# System.net
KiCad netlist of a schematic drawn in Altium Designer
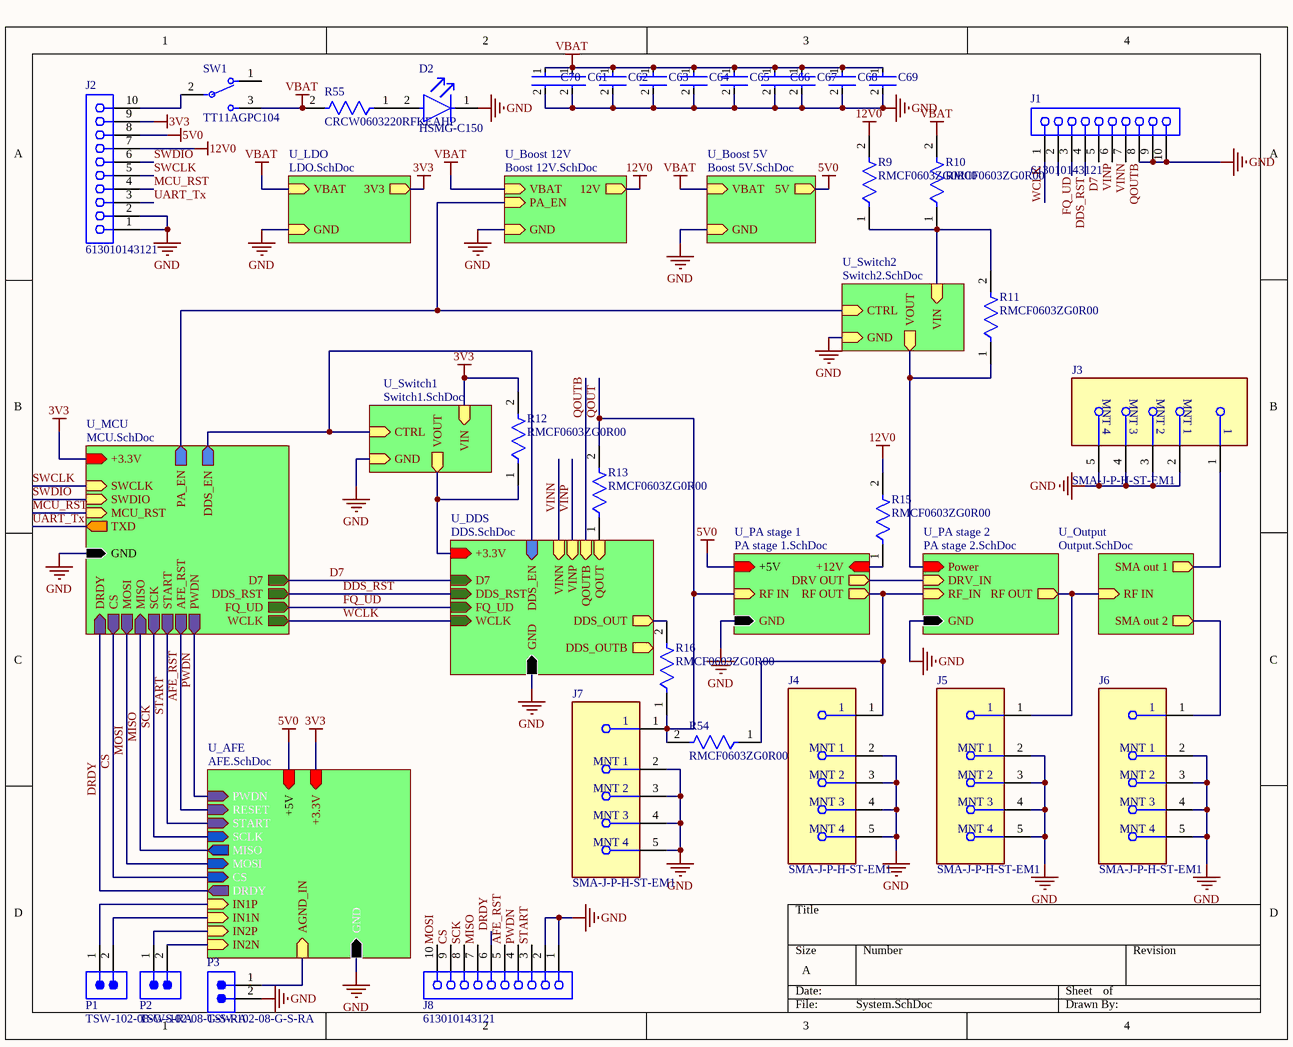
[diagram p0: System.SchDoc]

(export (version "E")
  (design (tool "Eeschema 10.0.6"))
  (components
    (comp (ref "C61")
      (value "GRM21BR60J107ME15K")
      (footprint "FP-GRM21B-0_2-e0_2_0_7-IPC_B")
      (description "Chip Multilayer Ceramic Capacitors for General Purpose, 0805, 100uF, X5R, 15%, 20%, 6.3V")
      (fields (field (name "TOLERANCE") "20%"))
      (libsource (lib "Altium Content Vault") (part "b4654b650e69147ec39a6b967a45e02"))
    )
    (comp (ref "C62")
      (value "GRM21BR60J107ME15K")
      (footprint "FP-GRM21B-0_2-e0_2_0_7-IPC_B")
      (description "Chip Multilayer Ceramic Capacitors for General Purpose, 0805, 100uF, X5R, 15%, 20%, 6.3V")
      (fields (field (name "TOLERANCE") "20%"))
      (libsource (lib "Altium Content Vault") (part "b4654b650e69147ec39a6b967a45e02"))
    )
    (comp (ref "C63")
      (value "GRM21BR60J107ME15K")
      (footprint "FP-GRM21B-0_2-e0_2_0_7-IPC_B")
      (description "Chip Multilayer Ceramic Capacitors for General Purpose, 0805, 100uF, X5R, 15%, 20%, 6.3V")
      (fields (field (name "TOLERANCE") "20%"))
      (libsource (lib "Altium Content Vault") (part "b4654b650e69147ec39a6b967a45e02"))
    )
    (comp (ref "C64")
      (value "GRM21BR60J107ME15K")
      (footprint "FP-GRM21B-0_2-e0_2_0_7-IPC_B")
      (description "Chip Multilayer Ceramic Capacitors for General Purpose, 0805, 100uF, X5R, 15%, 20%, 6.3V")
      (fields (field (name "TOLERANCE") "20%"))
      (libsource (lib "Altium Content Vault") (part "b4654b650e69147ec39a6b967a45e02"))
    )
    (comp (ref "C65")
      (value "GRM21BR60J107ME15K")
      (footprint "FP-GRM21B-0_2-e0_2_0_7-IPC_B")
      (description "Chip Multilayer Ceramic Capacitors for General Purpose, 0805, 100uF, X5R, 15%, 20%, 6.3V")
      (fields (field (name "TOLERANCE") "20%"))
      (libsource (lib "Altium Content Vault") (part "b4654b650e69147ec39a6b967a45e02"))
    )
    (comp (ref "C66")
      (value "GRM21BR60J107ME15K")
      (footprint "FP-GRM21B-0_2-e0_2_0_7-IPC_B")
      (description "Chip Multilayer Ceramic Capacitors for General Purpose, 0805, 100uF, X5R, 15%, 20%, 6.3V")
      (fields (field (name "TOLERANCE") "20%"))
      (libsource (lib "Altium Content Vault") (part "b4654b650e69147ec39a6b967a45e02"))
    )
    (comp (ref "C67")
      (value "GRM21BR60J107ME15K")
      (footprint "FP-GRM21B-0_2-e0_2_0_7-IPC_B")
      (description "Chip Multilayer Ceramic Capacitors for General Purpose, 0805, 100uF, X5R, 15%, 20%, 6.3V")
      (fields (field (name "TOLERANCE") "20%"))
      (libsource (lib "Altium Content Vault") (part "b4654b650e69147ec39a6b967a45e02"))
    )
    (comp (ref "C68")
      (value "GRM21BR60J107ME15K")
      (footprint "FP-GRM21B-0_2-e0_2_0_7-IPC_B")
      (description "Chip Multilayer Ceramic Capacitors for General Purpose, 0805, 100uF, X5R, 15%, 20%, 6.3V")
      (fields (field (name "TOLERANCE") "20%"))
      (libsource (lib "Altium Content Vault") (part "b4654b650e69147ec39a6b967a45e02"))
    )
    (comp (ref "C69")
      (value "GRM21BR60J107ME15K")
      (footprint "FP-GRM21B-0_2-e0_2_0_7-IPC_B")
      (description "Chip Multilayer Ceramic Capacitors for General Purpose, 0805, 100uF, X5R, 15%, 20%, 6.3V")
      (fields (field (name "TOLERANCE") "20%"))
      (libsource (lib "Altium Content Vault") (part "b4654b650e69147ec39a6b967a45e02"))
    )
    (comp (ref "C70")
      (value "GRM21BR60J107ME15K")
      (footprint "FP-GRM21B-0_2-e0_2_0_7-IPC_B")
      (description "Chip Multilayer Ceramic Capacitors for General Purpose, 0805, 100uF, X5R, 15%, 20%, 6.3V")
      (fields (field (name "TOLERANCE") "20%"))
      (libsource (lib "Altium Content Vault") (part "b4654b650e69147ec39a6b967a45e02"))
    )
    (comp (ref "D2")
      (value "HSMG-C150")
      (footprint "FP-HSMG-C150-MFG")
      (description "LED GREEN DIFFUSED 1206 SMD")
      (fields
        (field (name "MANUFACTURER") "Broadcom")
        (field (name "OCTOPART") "https://octopart.com/hsmg-c150-broadcom-71131304")
      )
      (libsource (lib "Altium Content Vault") (part "8706943c75ba83719d021d2fdc84c58"))
    )
    (comp (ref "J1")
      (value "613010143121")
      (footprint "613010143121")
      (libsource (lib "Altium Content Vault") (part "Header_Female_1R_10P"))
    )
    (comp (ref "J2")
      (value "613010143121")
      (footprint "613010143121")
      (libsource (lib "Altium Content Vault") (part "Header_Female_1R_10P"))
    )
    (comp (ref "J3")
      (value "SMA-J-P-H-ST-EM1")
      (footprint "FP-SMA-J-P-H-ST-EM1-MFG")
      (description "CONN SMA JACK STR 50OHM EDGE MNT")
      (libsource (lib "") (part "c65b8a639cdaef1819ea20b5466f8fa_1"))
    )
    (comp (ref "J4")
      (value "SMA-J-P-H-ST-EM1")
      (footprint "FP-SMA-J-P-H-ST-EM1-MFG")
      (description "CONN SMA JACK STR 50OHM EDGE MNT")
      (libsource (lib "Altium Content Vault") (part "c65b8a639cdaef1819ea20b5466f8fa"))
    )
    (comp (ref "J5")
      (value "SMA-J-P-H-ST-EM1")
      (footprint "FP-SMA-J-P-H-ST-EM1-MFG")
      (description "CONN SMA JACK STR 50OHM EDGE MNT")
      (libsource (lib "Altium Content Vault") (part "c65b8a639cdaef1819ea20b5466f8fa"))
    )
    (comp (ref "J6")
      (value "SMA-J-P-H-ST-EM1")
      (footprint "FP-SMA-J-P-H-ST-EM1-MFG")
      (description "CONN SMA JACK STR 50OHM EDGE MNT")
      (libsource (lib "Altium Content Vault") (part "c65b8a639cdaef1819ea20b5466f8fa"))
    )
    (comp (ref "J7")
      (value "SMA-J-P-H-ST-EM1")
      (footprint "FP-SMA-J-P-H-ST-EM1-MFG")
      (description "CONN SMA JACK STR 50OHM EDGE MNT")
      (libsource (lib "Altium Content Vault") (part "c65b8a639cdaef1819ea20b5466f8fa"))
    )
    (comp (ref "J8")
      (value "613010143121")
      (footprint "613010143121")
      (libsource (lib "Altium Content Vault") (part "Header_Female_1R_10P"))
    )
    (comp (ref "P1")
      (value "TSW-102-08-G-S-RA")
      (footprint "SMTC-TSW-102-08-X-S-RA")
      (fields (field (name "MANUFACTURER") "Samtec"))
      (libsource (lib "Altium Content Vault") (part "SMTC-TSW-102-X-X-S-X"))
    )
    (comp (ref "P2")
      (value "TSW-102-08-G-S-RA")
      (footprint "SMTC-TSW-102-08-X-S-RA")
      (fields (field (name "MANUFACTURER") "Samtec"))
      (libsource (lib "Altium Content Vault") (part "SMTC-TSW-102-X-X-S-X"))
    )
    (comp (ref "P3")
      (value "TSW-102-08-G-S-RA")
      (footprint "SMTC-TSW-102-08-X-S-RA")
      (fields (field (name "MANUFACTURER") "Samtec"))
      (libsource (lib "Altium Content Vault") (part "SMTC-TSW-102-X-X-S-X"))
    )
    (comp (ref "R9")
      (value "RMCF0603ZG0R00")
      (footprint "FP-RMCF0603-IPC_B")
      (description "0Ω ±0 0.1W 0603 Thick Film Chip Resistor AEC-Q200 compliant")
      (libsource (lib "Altium Content Vault") (part "1029c3af85768c4190bb7ad29bc67b5"))
    )
    (comp (ref "R10")
      (value "RMCF0603ZG0R00")
      (footprint "FP-RMCF0603-IPC_B")
      (description "0Ω ±0 0.1W 0603 Thick Film Chip Resistor AEC-Q200 compliant")
      (libsource (lib "Altium Content Vault") (part "1029c3af85768c4190bb7ad29bc67b5"))
    )
    (comp (ref "R11")
      (value "RMCF0603ZG0R00")
      (footprint "FP-RMCF0603-IPC_B")
      (description "0Ω ±0 0.1W 0603 Thick Film Chip Resistor AEC-Q200 compliant")
      (libsource (lib "Altium Content Vault") (part "1029c3af85768c4190bb7ad29bc67b5"))
    )
    (comp (ref "R12")
      (value "RMCF0603ZG0R00")
      (footprint "FP-RMCF0603-IPC_B")
      (description "0Ω ±0 0.1W 0603 Thick Film Chip Resistor AEC-Q200 compliant")
      (libsource (lib "Altium Content Vault") (part "1029c3af85768c4190bb7ad29bc67b5"))
    )
    (comp (ref "R13")
      (value "RMCF0603ZG0R00")
      (footprint "FP-RMCF0603-IPC_B")
      (description "0Ω ±0 0.1W 0603 Thick Film Chip Resistor AEC-Q200 compliant")
      (libsource (lib "Altium Content Vault") (part "1029c3af85768c4190bb7ad29bc67b5"))
    )
    (comp (ref "R15")
      (value "RMCF0603ZG0R00")
      (footprint "FP-RMCF0603-IPC_B")
      (description "0Ω ±0 0.1W 0603 Thick Film Chip Resistor AEC-Q200 compliant")
      (libsource (lib "Altium Content Vault") (part "1029c3af85768c4190bb7ad29bc67b5"))
    )
    (comp (ref "R16")
      (value "RMCF0603ZG0R00")
      (footprint "FP-RMCF0603-IPC_B")
      (description "0Ω ±0 0.1W 0603 Thick Film Chip Resistor AEC-Q200 compliant")
      (libsource (lib "Altium Content Vault") (part "1029c3af85768c4190bb7ad29bc67b5"))
    )
    (comp (ref "R54")
      (value "RMCF0603ZG0R00")
      (footprint "FP-RMCF0603-IPC_B")
      (description "0Ω ±0 0.1W 0603 Thick Film Chip Resistor AEC-Q200 compliant")
      (libsource (lib "Altium Content Vault") (part "1029c3af85768c4190bb7ad29bc67b5"))
    )
    (comp (ref "R55")
      (value "CRCW0603220RFKEAHP")
      (footprint "FP-CRCW0603-HPe3-IPC_A")
      (description "RES Thick Film, 220Ω, 1%, 0.33W, 100ppm/°C, 0603")
      (fields (field (name "TOLERANCE") "1%"))
      (libsource (lib "Altium Content Vault") (part "1029c3af85768c4190bb7ad29bc67b5"))
    )
    (comp (ref "SW1")
      (value "TT11AGPC104")
      (footprint "FP-TT11AGPC104-MFG")
      (description "SWITCH TOGGLE SPST 0.4VA 20V")
      (libsource (lib "Altium Content Vault") (part "52c419afdc2a387c7d548259a9aeefb"))
    )
  )
  (nets
    (net (code "1") (name "/+12V") (class "Default")
      (node (ref "R15") (pin "1") (pinfunction "1_1") (pintype "passive"))
    )
    (net (code "2") (name "/AFE_RST") (class "Default")
      (node (ref "J8") (pin "5") (pinfunction "5_5") (pintype "passive"))
    )
    (net (code "3") (name "/AGND_IN") (class "Default")
      (node (ref "P3") (pin "1") (pinfunction "1_1") (pintype "passive"))
    )
    (net (code "4") (name "/CS") (class "Default")
      (node (ref "J8") (pin "9") (pinfunction "9_9") (pintype "passive"))
    )
    (net (code "5") (name "/D7") (class "Default")
      (node (ref "J1") (pin "4") (pinfunction "4_4") (pintype "passive"))
    )
    (net (code "7") (name "/DDS_OUT") (class "Default")
      (node (ref "R16") (pin "2") (pinfunction "2_2") (pintype "passive"))
    )
    (net (code "9") (name "/DDS_RST") (class "Default")
      (node (ref "J1") (pin "3") (pinfunction "3_3") (pintype "passive"))
    )
    (net (code "10") (name "/DRDY") (class "Default")
      (node (ref "J8") (pin "6") (pinfunction "6_6") (pintype "passive"))
    )
    (net (code "12") (name "/FQ_UD") (class "Default")
      (node (ref "J1") (pin "2") (pinfunction "2_2") (pintype "passive"))
    )
    (net (code "13") (name "/IN1N") (class "Default")
      (node (ref "P1") (pin "2") (pinfunction "2_2") (pintype "passive"))
    )
    (net (code "14") (name "/IN1P") (class "Default")
      (node (ref "P1") (pin "1") (pinfunction "1_1") (pintype "passive"))
    )
    (net (code "15") (name "/IN2N") (class "Default")
      (node (ref "P2") (pin "2") (pinfunction "2_2") (pintype "passive"))
    )
    (net (code "16") (name "/IN2P") (class "Default")
      (node (ref "P2") (pin "1") (pinfunction "1_1") (pintype "passive"))
    )
    (net (code "17") (name "/MCU_RST") (class "Default")
      (node (ref "J2") (pin "4") (pinfunction "4_4") (pintype "passive"))
    )
    (net (code "18") (name "/MISO") (class "Default")
      (node (ref "J8") (pin "7") (pinfunction "7_7") (pintype "passive"))
    )
    (net (code "19") (name "/MOSI") (class "Default")
      (node (ref "J8") (pin "10") (pinfunction "10_10") (pintype "passive"))
    )
    (net (code "21") (name "/PWDN") (class "Default")
      (node (ref "J8") (pin "4") (pinfunction "4_4") (pintype "passive"))
    )
    (net (code "22") (name "/QOUT") (class "Default")
      (node (ref "J7") (pin "1") (pinfunction "1_1") (pintype "passive"))
      (node (ref "R13") (pin "2") (pinfunction "2_2") (pintype "passive"))
      (node (ref "R16") (pin "1") (pinfunction "1_1") (pintype "passive"))
      (node (ref "R54") (pin "2") (pinfunction "2_2") (pintype "passive"))
    )
    (net (code "23") (name "/QOUTB") (class "Default")
      (node (ref "J1") (pin "7") (pinfunction "7_7") (pintype "passive"))
    )
    (net (code "24") (name "/QOUT_1") (class "Default")
      (node (ref "R13") (pin "1") (pinfunction "1_1") (pintype "passive"))
    )
    (net (code "25") (name "/RF OUT") (class "Default")
      (node (ref "J4") (pin "1") (pinfunction "1_1") (pintype "passive"))
      (node (ref "R54") (pin "1") (pinfunction "1_1") (pintype "passive"))
    )
    (net (code "26") (name "/RF OUT_1") (class "Default")
      (node (ref "J5") (pin "1") (pinfunction "1_1") (pintype "passive"))
    )
    (net (code "27") (name "/SCK") (class "Default")
      (node (ref "J8") (pin "8") (pinfunction "8_8") (pintype "passive"))
    )
    (net (code "28") (name "/SMA out 1") (class "Default")
      (node (ref "J3") (pin "1") (pinfunction "1_1") (pintype "passive"))
    )
    (net (code "29") (name "/SMA out 2") (class "Default")
      (node (ref "J6") (pin "1") (pinfunction "1_1") (pintype "passive"))
    )
    (net (code "30") (name "/START") (class "Default")
      (node (ref "J8") (pin "3") (pinfunction "3_3") (pintype "passive"))
    )
    (net (code "31") (name "/SWCLK") (class "Default")
      (node (ref "J2") (pin "5") (pinfunction "5_5") (pintype "passive"))
    )
    (net (code "32") (name "/SWDIO") (class "Default")
      (node (ref "J2") (pin "6") (pinfunction "6_6") (pintype "passive"))
    )
    (net (code "33") (name "/UART_Tx") (class "Default")
      (node (ref "J2") (pin "3") (pinfunction "3_3") (pintype "passive"))
    )
    (net (code "34") (name "/VIN") (class "Default")
      (node (ref "R10") (pin "1") (pinfunction "1_1") (pintype "passive"))
      (node (ref "R11") (pin "2") (pinfunction "2_2") (pintype "passive"))
      (node (ref "R9") (pin "1") (pinfunction "1_1") (pintype "passive"))
    )
    (net (code "35") (name "/VINN") (class "Default")
      (node (ref "J1") (pin "6") (pinfunction "6_6") (pintype "passive"))
    )
    (net (code "36") (name "/VINP") (class "Default")
      (node (ref "J1") (pin "5") (pinfunction "5_5") (pintype "passive"))
    )
    (net (code "37") (name "/VOUT") (class "Default")
      (node (ref "R11") (pin "1") (pinfunction "1_1") (pintype "passive"))
    )
    (net (code "38") (name "/VOUT_1") (class "Default")
      (node (ref "R12") (pin "1") (pinfunction "1_1") (pintype "passive"))
    )
    (net (code "39") (name "/WCLK") (class "Default")
      (node (ref "J1") (pin "1") (pinfunction "1_1") (pintype "passive"))
    )
    (net (code "40") (name "3V3") (class "Default")
      (node (ref "J2") (pin "9") (pinfunction "9_9") (pintype "passive"))
      (node (ref "R12") (pin "2") (pinfunction "2_2") (pintype "passive"))
    )
    (net (code "41") (name "5V0") (class "Default")
      (node (ref "J2") (pin "8") (pinfunction "8_8") (pintype "passive"))
    )
    (net (code "42") (name "12V0") (class "Default")
      (node (ref "J2") (pin "7") (pinfunction "7_7") (pintype "passive"))
      (node (ref "R15") (pin "2") (pinfunction "2_2") (pintype "passive"))
      (node (ref "R9") (pin "2") (pinfunction "2_2") (pintype "passive"))
    )
    (net (code "43") (name "GND") (class "Default")
      (node (ref "C61") (pin "2") (pinfunction "2_2") (pintype "passive"))
      (node (ref "C62") (pin "2") (pinfunction "2_2") (pintype "passive"))
      (node (ref "C63") (pin "2") (pinfunction "2_2") (pintype "passive"))
      (node (ref "C64") (pin "2") (pinfunction "2_2") (pintype "passive"))
      (node (ref "C65") (pin "2") (pinfunction "2_2") (pintype "passive"))
      (node (ref "C66") (pin "2") (pinfunction "2_2") (pintype "passive"))
      (node (ref "C67") (pin "2") (pinfunction "2_2") (pintype "passive"))
      (node (ref "C68") (pin "2") (pinfunction "2_2") (pintype "passive"))
      (node (ref "C69") (pin "2") (pinfunction "2_2") (pintype "passive"))
      (node (ref "C70") (pin "2") (pinfunction "2_2") (pintype "passive"))
      (node (ref "D2") (pin "1") (pinfunction "C_1") (pintype "passive"))
      (node (ref "J1") (pin "10") (pinfunction "10_10") (pintype "passive"))
      (node (ref "J1") (pin "8") (pinfunction "8_8") (pintype "passive"))
      (node (ref "J1") (pin "9") (pinfunction "9_9") (pintype "passive"))
      (node (ref "J2") (pin "1") (pinfunction "1_1") (pintype "passive"))
      (node (ref "J2") (pin "2") (pinfunction "2_2") (pintype "passive"))
      (node (ref "J3") (pin "2") (pinfunction "MNT_1_2") (pintype "passive"))
      (node (ref "J3") (pin "3") (pinfunction "MNT_2_3") (pintype "passive"))
      (node (ref "J3") (pin "4") (pinfunction "MNT_3_4") (pintype "passive"))
      (node (ref "J3") (pin "5") (pinfunction "MNT_4_5") (pintype "passive"))
      (node (ref "J4") (pin "2") (pinfunction "MNT_1_2") (pintype "passive"))
      (node (ref "J4") (pin "3") (pinfunction "MNT_2_3") (pintype "passive"))
      (node (ref "J4") (pin "4") (pinfunction "MNT_3_4") (pintype "passive"))
      (node (ref "J4") (pin "5") (pinfunction "MNT_4_5") (pintype "passive"))
      (node (ref "J5") (pin "2") (pinfunction "MNT_1_2") (pintype "passive"))
      (node (ref "J5") (pin "3") (pinfunction "MNT_2_3") (pintype "passive"))
      (node (ref "J5") (pin "4") (pinfunction "MNT_3_4") (pintype "passive"))
      (node (ref "J5") (pin "5") (pinfunction "MNT_4_5") (pintype "passive"))
      (node (ref "J6") (pin "2") (pinfunction "MNT_1_2") (pintype "passive"))
      (node (ref "J6") (pin "3") (pinfunction "MNT_2_3") (pintype "passive"))
      (node (ref "J6") (pin "4") (pinfunction "MNT_3_4") (pintype "passive"))
      (node (ref "J6") (pin "5") (pinfunction "MNT_4_5") (pintype "passive"))
      (node (ref "J7") (pin "2") (pinfunction "MNT_1_2") (pintype "passive"))
      (node (ref "J7") (pin "3") (pinfunction "MNT_2_3") (pintype "passive"))
      (node (ref "J7") (pin "4") (pinfunction "MNT_3_4") (pintype "passive"))
      (node (ref "J7") (pin "5") (pinfunction "MNT_4_5") (pintype "passive"))
      (node (ref "J8") (pin "1") (pinfunction "1_1") (pintype "passive"))
      (node (ref "J8") (pin "2") (pinfunction "2_2") (pintype "passive"))
      (node (ref "P3") (pin "2") (pinfunction "2_2") (pintype "passive"))
    )
    (net (code "44") (name "Net-(D2-A)") (class "Default")
      (node (ref "D2") (pin "2") (pinfunction "A_2") (pintype "passive"))
      (node (ref "R55") (pin "1") (pinfunction "1_1") (pintype "passive"))
    )
    (net (code "45") (name "Net-(J2-Pad10)") (class "Default")
      (node (ref "J2") (pin "10") (pinfunction "10_10") (pintype "passive"))
      (node (ref "SW1") (pin "2") (pinfunction "2_2") (pintype "passive"))
    )
    (net (code "46") (name "VBAT") (class "Default")
      (node (ref "C61") (pin "1") (pinfunction "1_1") (pintype "passive"))
      (node (ref "C62") (pin "1") (pinfunction "1_1") (pintype "passive"))
      (node (ref "C63") (pin "1") (pinfunction "1_1") (pintype "passive"))
      (node (ref "C64") (pin "1") (pinfunction "1_1") (pintype "passive"))
      (node (ref "C65") (pin "1") (pinfunction "1_1") (pintype "passive"))
      (node (ref "C66") (pin "1") (pinfunction "1_1") (pintype "passive"))
      (node (ref "C67") (pin "1") (pinfunction "1_1") (pintype "passive"))
      (node (ref "C68") (pin "1") (pinfunction "1_1") (pintype "passive"))
      (node (ref "C69") (pin "1") (pinfunction "1_1") (pintype "passive"))
      (node (ref "C70") (pin "1") (pinfunction "1_1") (pintype "passive"))
      (node (ref "R10") (pin "2") (pinfunction "2_2") (pintype "passive"))
      (node (ref "R55") (pin "2") (pinfunction "2_2") (pintype "passive"))
      (node (ref "SW1") (pin "3") (pinfunction "3_3") (pintype "passive"))
    )
    (net (code "47") (name "unconnected-(SW1-Pad1)") (class "Default")
      (node (ref "SW1") (pin "1") (pinfunction "1_1") (pintype "passive"))
    )
  )
)
